# 1__schdoc.net
KiCad netlist of a schematic drawn in Altium Designer
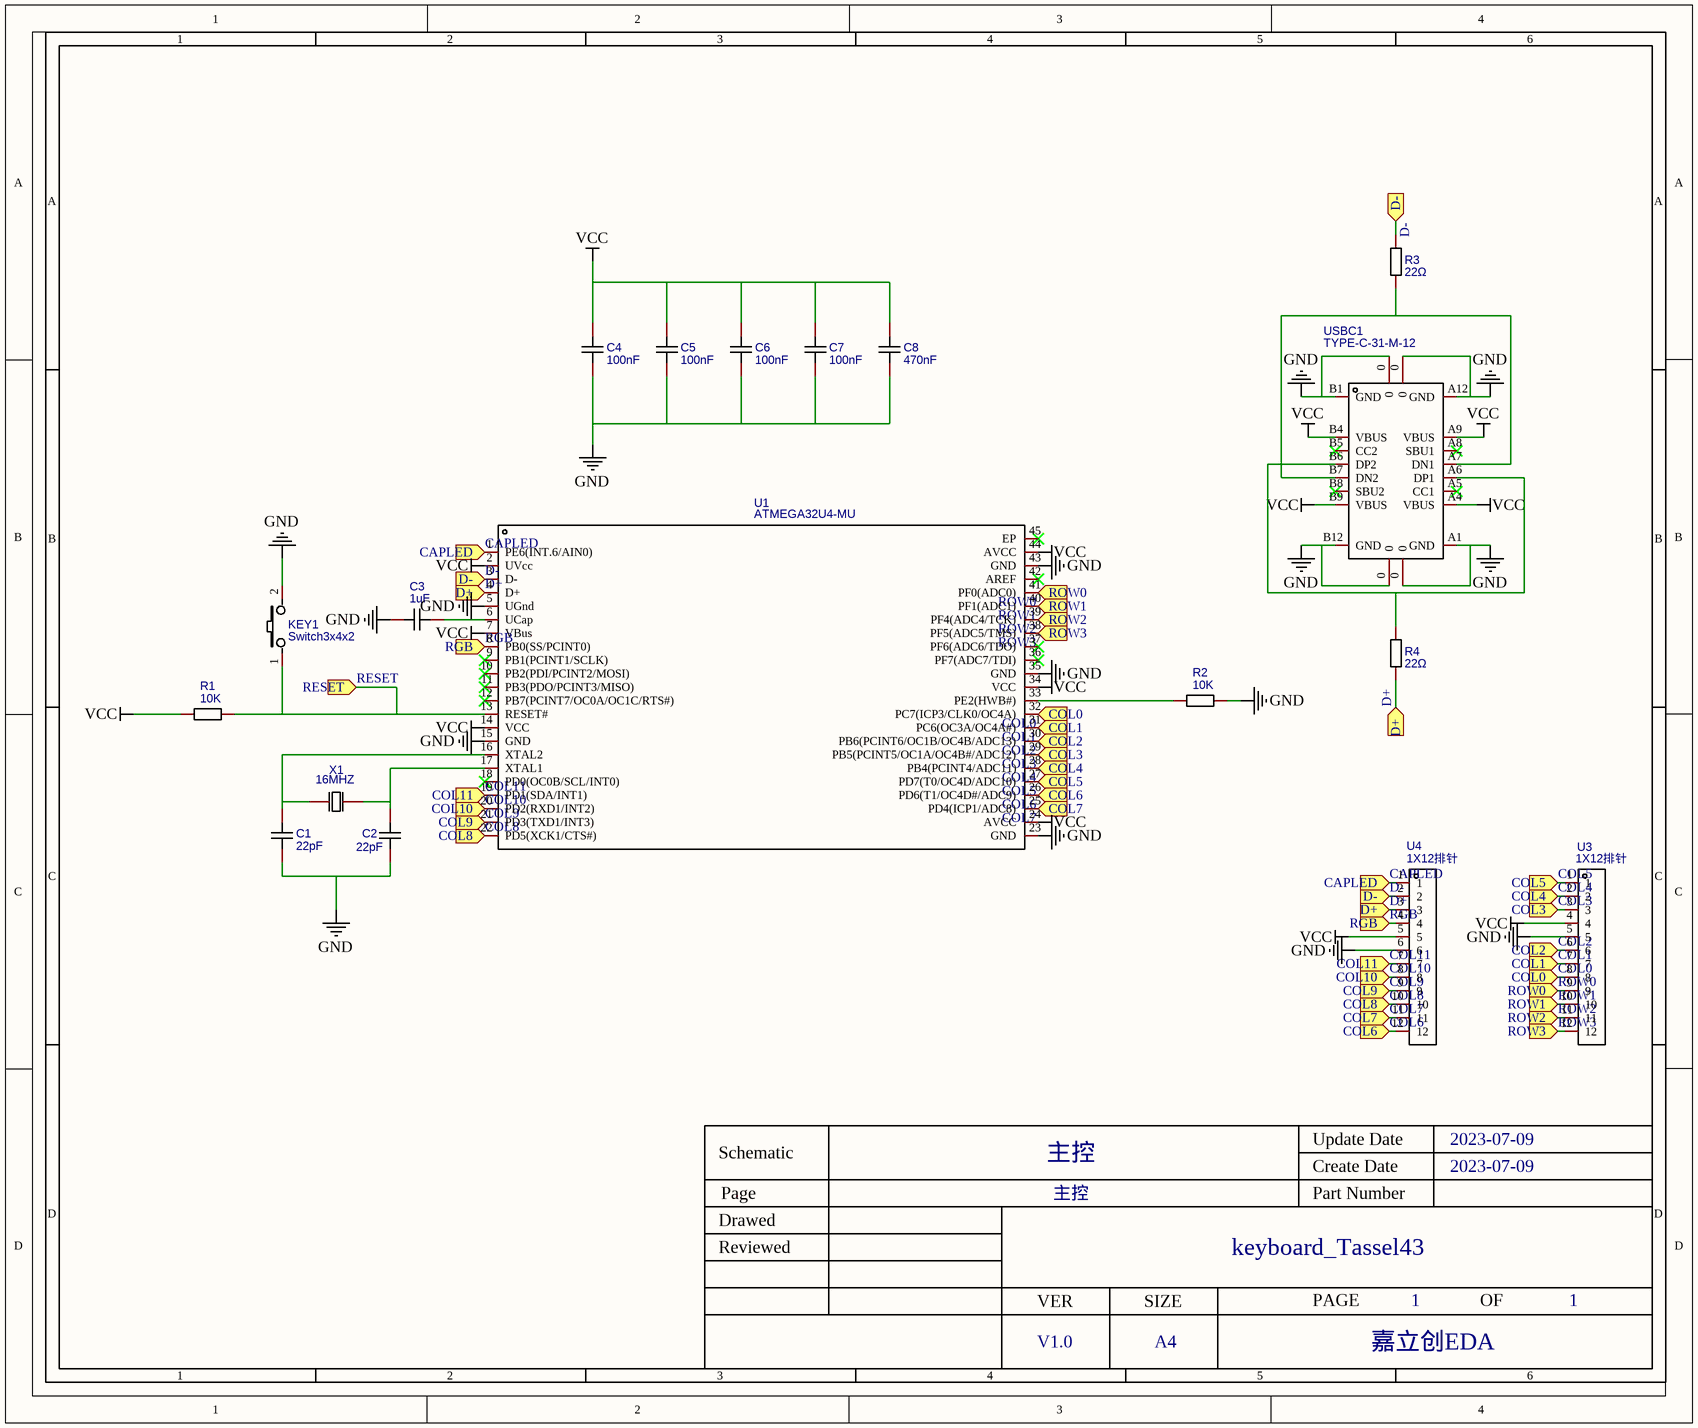
[diagram p0: 1_主控.schdoc.schdoc]

(export (version "E")
  (design (tool "Eeschema 10.0.6"))
  (components
    (comp (ref "C1")
      (value "22pF")
      (fields
        (field (name "NAME") "22pF")
        (field (name "MANUFACTURER") "Huaxin ST")
        (field (name "MANUFACTURER PART") "0603N220F101CT")
      )
      (libsource (lib "altium-import") (part "root_0_0603N220F101CT_"))
    )
    (comp (ref "C2")
      (value "22pF")
      (fields
        (field (name "NAME") "22pF")
        (field (name "MANUFACTURER") "Huaxin ST")
        (field (name "MANUFACTURER PART") "0603N220F101CT")
      )
      (libsource (lib "altium-import") (part "root_0_0603N220F101CT_"))
    )
    (comp (ref "C3")
      (value "1uF")
      (fields
        (field (name "NAME") "1uF")
        (field (name "MANUFACTURER") "FH")
        (field (name "MANUFACTURER PART") "0603B105K500NT")
      )
      (libsource (lib "altium-import") (part "root_0_0603B105K500NT_"))
    )
    (comp (ref "C4")
      (value "100nF")
      (fields
        (field (name "NAME") "100nF")
        (field (name "MANUFACTURER") "FH")
        (field (name "MANUFACTURER PART") "0603B104J500NT")
      )
      (libsource (lib "altium-import") (part "root_1_0603B104J500NT_"))
    )
    (comp (ref "C5")
      (value "100nF")
      (fields
        (field (name "NAME") "100nF")
        (field (name "MANUFACTURER") "FH")
        (field (name "MANUFACTURER PART") "0603B104J500NT")
      )
      (libsource (lib "altium-import") (part "root_1_0603B104J500NT_"))
    )
    (comp (ref "C6")
      (value "100nF")
      (fields
        (field (name "NAME") "100nF")
        (field (name "MANUFACTURER") "FH")
        (field (name "MANUFACTURER PART") "0603B104J500NT")
      )
      (libsource (lib "altium-import") (part "root_1_0603B104J500NT_"))
    )
    (comp (ref "C7")
      (value "100nF")
      (fields
        (field (name "NAME") "100nF")
        (field (name "MANUFACTURER") "FH")
        (field (name "MANUFACTURER PART") "0603B104J500NT")
      )
      (libsource (lib "altium-import") (part "root_1_0603B104J500NT_"))
    )
    (comp (ref "C8")
      (value "470nF")
      (fields
        (field (name "NAME") "470nF")
        (field (name "MANUFACTURER") "FH")
        (field (name "MANUFACTURER PART") "0603B474K250NT")
      )
      (libsource (lib "altium-import") (part "root_1_0603B474K250NT_"))
    )
    (comp (ref "KEY1")
      (value "Switch3x4x2")
      (fields (field (name "NAME") "Switch3x4x2") (field (name "MANUFACTURER") "ReliaPro"))
      (libsource (lib "altium-import") (part "root_1_Switch3x4x2_"))
    )
    (comp (ref "R1")
      (value "10K")
      (fields
        (field (name "NAME") "10K")
        (field (name "MANUFACTURER") "YAGEO")
        (field (name "MANUFACTURER PART") "AC0603FR-0710KL")
      )
      (libsource (lib "altium-import") (part "root_0_AC0603FR-0710KL_"))
    )
    (comp (ref "R2")
      (value "10K")
      (fields
        (field (name "NAME") "10K")
        (field (name "MANUFACTURER") "YAGEO")
        (field (name "MANUFACTURER PART") "AC0603FR-0710KL")
      )
      (libsource (lib "altium-import") (part "root_0_AC0603FR-0710KL_"))
    )
    (comp (ref "R3")
      (value "22Ω")
      (fields
        (field (name "NAME") "22Ω")
        (field (name "MANUFACTURER") "LIZ")
        (field (name "MANUFACTURER PART") "CR0603JA0220G")
      )
      (libsource (lib "altium-import") (part "root_1_CR0603JA0220G_"))
    )
    (comp (ref "R4")
      (value "22Ω")
      (fields
        (field (name "NAME") "22Ω")
        (field (name "MANUFACTURER") "LIZ")
        (field (name "MANUFACTURER PART") "CR0603JA0220G")
      )
      (libsource (lib "altium-import") (part "root_1_CR0603JA0220G_"))
    )
    (comp (ref "U1")
      (value "ATMEGA32U4-MU")
      (fields (field (name "NAME") "ATMEGA32U4-MU") (field (name "MANUFACTURER") "MICROCHIP"))
      (libsource (lib "altium-import") (part "root_0_ATMEGA32U4-MU_"))
    )
    (comp (ref "U3")
      (value "1X12排针")
      (fields (field (name "NAME") "1X12排针"))
      (libsource (lib "altium-import") (part "root_0_1X12排针_"))
    )
    (comp (ref "U4")
      (value "1X12排针")
      (fields (field (name "NAME") "1X12排针"))
      (libsource (lib "altium-import") (part "root_0_1X12排针_"))
    )
    (comp (ref "USBC1")
      (value "TYPE-C-31-M-12")
      (fields
        (field (name "NAME") "TYPE-C-31-M-12")
        (field (name "MANUFACTURER") "RectangularConnectors-Contacts")
      )
      (libsource (lib "altium-import") (part "root_0_TYPE-C-31-M-12_"))
    )
    (comp (ref "X1")
      (value "16MHZ")
      (fields
        (field (name "NAME") "16MHZ")
        (field (name "MANUFACTURER") "TAITIEN Elec")
        (field (name "MANUFACTURER PART") "XSHEELNANF-16MHZ")
      )
      (libsource (lib "altium-import") (part "root_0_XSHEELNANF-16MHZ_"))
    )
  )
  (nets
    (net (code "1") (name "/CAPLED") (class "Default")
      (node (ref "U1") (pin "1") (pinfunction "PE6(INT.6/AIN0)_1") (pintype "passive"))
      (node (ref "U4") (pin "1") (pinfunction "1_1") (pintype "passive"))
    )
    (net (code "2") (name "/COL0") (class "Default")
      (node (ref "U1") (pin "32") (pinfunction "PC7(ICP3/CLK0/OC4A)_32") (pintype "passive"))
      (node (ref "U3") (pin "8") (pinfunction "8_8") (pintype "passive"))
    )
    (net (code "3") (name "/COL1") (class "Default")
      (node (ref "U1") (pin "31") (pinfunction "PC6(OC3A/OC4A#)_31") (pintype "passive"))
      (node (ref "U3") (pin "7") (pinfunction "7_7") (pintype "passive"))
    )
    (net (code "4") (name "/COL2") (class "Default")
      (node (ref "U1") (pin "30") (pinfunction "PB6(PCINT6/OC1B/OC4B/ADC13)_30") (pintype "passive"))
      (node (ref "U3") (pin "6") (pinfunction "6_6") (pintype "passive"))
    )
    (net (code "5") (name "/COL3") (class "Default")
      (node (ref "U1") (pin "29") (pinfunction "PB5(PCINT5/OC1A/OC4B#/ADC12)_29") (pintype "passive"))
      (node (ref "U3") (pin "3") (pinfunction "3_3") (pintype "passive"))
    )
    (net (code "6") (name "/COL4") (class "Default")
      (node (ref "U1") (pin "28") (pinfunction "PB4(PCINT4/ADC11)_28") (pintype "passive"))
      (node (ref "U3") (pin "2") (pinfunction "2_2") (pintype "passive"))
    )
    (net (code "7") (name "/COL5") (class "Default")
      (node (ref "U1") (pin "27") (pinfunction "PD7(T0/OC4D/ADC10)_27") (pintype "passive"))
      (node (ref "U3") (pin "1") (pinfunction "1_1") (pintype "passive"))
    )
    (net (code "8") (name "/COL6") (class "Default")
      (node (ref "U1") (pin "26") (pinfunction "PD6(T1/OC4D#/ADC9)_26") (pintype "passive"))
      (node (ref "U4") (pin "12") (pinfunction "12_12") (pintype "passive"))
    )
    (net (code "9") (name "/COL7") (class "Default")
      (node (ref "U1") (pin "25") (pinfunction "PD4(ICP1/ADC8)_25") (pintype "passive"))
      (node (ref "U4") (pin "11") (pinfunction "11_11") (pintype "passive"))
    )
    (net (code "10") (name "/COL8") (class "Default")
      (node (ref "U1") (pin "22") (pinfunction "PD5(XCK1/CTS#)_22") (pintype "passive"))
      (node (ref "U4") (pin "10") (pinfunction "10_10") (pintype "passive"))
    )
    (net (code "11") (name "/COL9") (class "Default")
      (node (ref "U1") (pin "21") (pinfunction "PD3(TXD1/INT3)_21") (pintype "passive"))
      (node (ref "U4") (pin "9") (pinfunction "9_9") (pintype "passive"))
    )
    (net (code "12") (name "/COL10") (class "Default")
      (node (ref "U1") (pin "20") (pinfunction "PD2(RXD1/INT2)_20") (pintype "passive"))
      (node (ref "U4") (pin "8") (pinfunction "8_8") (pintype "passive"))
    )
    (net (code "13") (name "/COL11") (class "Default")
      (node (ref "U1") (pin "19") (pinfunction "PD1(SDA/INT1)_19") (pintype "passive"))
      (node (ref "U4") (pin "7") (pinfunction "7_7") (pintype "passive"))
    )
    (net (code "14") (name "/D+") (class "Default")
      (node (ref "R4") (pin "1") (pinfunction "1_1") (pintype "passive"))
      (node (ref "U1") (pin "4") (pinfunction "D+_4") (pintype "passive"))
      (node (ref "U4") (pin "3") (pinfunction "3_3") (pintype "passive"))
    )
    (net (code "15") (name "/D-") (class "Default")
      (node (ref "R3") (pin "2") (pinfunction "2_2") (pintype "passive"))
      (node (ref "U1") (pin "3") (pinfunction "D-_3") (pintype "passive"))
      (node (ref "U4") (pin "2") (pinfunction "2_2") (pintype "passive"))
    )
    (net (code "16") (name "/RESET") (class "Default")
      (node (ref "KEY1") (pin "1") (pinfunction "1_1") (pintype "passive"))
      (node (ref "R1") (pin "2") (pinfunction "2_2") (pintype "passive"))
      (node (ref "U1") (pin "13") (pinfunction "RESET#_13") (pintype "passive"))
    )
    (net (code "17") (name "/RGB") (class "Default")
      (node (ref "U1") (pin "8") (pinfunction "PB0(SS/PCINT0)_8") (pintype "passive"))
      (node (ref "U4") (pin "4") (pinfunction "4_4") (pintype "passive"))
    )
    (net (code "18") (name "/ROW0") (class "Default")
      (node (ref "U1") (pin "41") (pinfunction "PF0(ADC0)_41") (pintype "passive"))
      (node (ref "U3") (pin "9") (pinfunction "9_9") (pintype "passive"))
    )
    (net (code "19") (name "/ROW1") (class "Default")
      (node (ref "U1") (pin "40") (pinfunction "PF1(ADC1)_40") (pintype "passive"))
      (node (ref "U3") (pin "10") (pinfunction "10_10") (pintype "passive"))
    )
    (net (code "20") (name "/ROW2") (class "Default")
      (node (ref "U1") (pin "39") (pinfunction "PF4(ADC4/TCK)_39") (pintype "passive"))
      (node (ref "U3") (pin "11") (pinfunction "11_11") (pintype "passive"))
    )
    (net (code "21") (name "/ROW3") (class "Default")
      (node (ref "U1") (pin "38") (pinfunction "PF5(ADC5/TMS)_38") (pintype "passive"))
      (node (ref "U3") (pin "12") (pinfunction "12_12") (pintype "passive"))
    )
    (net (code "22") (name "GND") (class "Default")
      (node (ref "C1") (pin "1") (pinfunction "1_1") (pintype "passive"))
      (node (ref "C2") (pin "1") (pinfunction "1_1") (pintype "passive"))
      (node (ref "C3") (pin "1") (pinfunction "1_1") (pintype "passive"))
      (node (ref "C4") (pin "1") (pinfunction "1_1") (pintype "passive"))
      (node (ref "C5") (pin "1") (pinfunction "1_1") (pintype "passive"))
      (node (ref "C6") (pin "1") (pinfunction "1_1") (pintype "passive"))
      (node (ref "C7") (pin "1") (pinfunction "1_1") (pintype "passive"))
      (node (ref "C8") (pin "2") (pinfunction "2_2") (pintype "passive"))
      (node (ref "KEY1") (pin "2") (pinfunction "2_2") (pintype "passive"))
      (node (ref "R2") (pin "2") (pinfunction "2_2") (pintype "passive"))
      (node (ref "U1") (pin "15") (pinfunction "GND_15") (pintype "passive"))
      (node (ref "U1") (pin "23") (pinfunction "GND_23") (pintype "passive"))
      (node (ref "U1") (pin "35") (pinfunction "GND_35") (pintype "passive"))
      (node (ref "U1") (pin "43") (pinfunction "GND_43") (pintype "passive"))
      (node (ref "U1") (pin "5") (pinfunction "UGnd_5") (pintype "passive"))
      (node (ref "U3") (pin "5") (pinfunction "5_5") (pintype "passive"))
      (node (ref "U4") (pin "6") (pinfunction "6_6") (pintype "passive"))
      (node (ref "USBC1") (pin "0") (pinfunction "0_0") (pintype "passive"))
      (node (ref "USBC1") (pin "A1") (pinfunction "GND_A1") (pintype "passive"))
      (node (ref "USBC1") (pin "A12") (pinfunction "GND_A12") (pintype "passive"))
      (node (ref "USBC1") (pin "B1") (pinfunction "GND_B1") (pintype "passive"))
      (node (ref "USBC1") (pin "B12") (pinfunction "GND_B12") (pintype "passive"))
    )
    (net (code "23") (name "Net-(U1-PE2(HWB#))") (class "Default")
      (node (ref "R2") (pin "1") (pinfunction "1_1") (pintype "passive"))
      (node (ref "U1") (pin "33") (pinfunction "PE2(HWB#)_33") (pintype "passive"))
    )
    (net (code "24") (name "Net-(U1-UCap)") (class "Default")
      (node (ref "C3") (pin "2") (pinfunction "2_2") (pintype "passive"))
      (node (ref "U1") (pin "6") (pinfunction "UCap_6") (pintype "passive"))
    )
    (net (code "25") (name "Net-(U1-XTAL1)") (class "Default")
      (node (ref "C2") (pin "2") (pinfunction "2_2") (pintype "passive"))
      (node (ref "U1") (pin "17") (pinfunction "XTAL1_17") (pintype "passive"))
      (node (ref "X1") (pin "2") (pinfunction "OSC2_2") (pintype "passive"))
    )
    (net (code "26") (name "Net-(U1-XTAL2)") (class "Default")
      (node (ref "C1") (pin "2") (pinfunction "2_2") (pintype "passive"))
      (node (ref "U1") (pin "16") (pinfunction "XTAL2_16") (pintype "passive"))
      (node (ref "X1") (pin "1") (pinfunction "OSC1_1") (pintype "passive"))
    )
    (net (code "27") (name "Net-(USBC1-DN1)") (class "Default")
      (node (ref "R3") (pin "1") (pinfunction "1_1") (pintype "passive"))
      (node (ref "USBC1") (pin "A7") (pinfunction "DN1_A7") (pintype "passive"))
      (node (ref "USBC1") (pin "B7") (pinfunction "DN2_B7") (pintype "passive"))
    )
    (net (code "28") (name "Net-(USBC1-DP1)") (class "Default")
      (node (ref "R4") (pin "2") (pinfunction "2_2") (pintype "passive"))
      (node (ref "USBC1") (pin "A6") (pinfunction "DP1_A6") (pintype "passive"))
      (node (ref "USBC1") (pin "B6") (pinfunction "DP2_B6") (pintype "passive"))
    )
    (net (code "29") (name "VCC") (class "Default")
      (node (ref "C4") (pin "2") (pinfunction "2_2") (pintype "passive"))
      (node (ref "C5") (pin "2") (pinfunction "2_2") (pintype "passive"))
      (node (ref "C6") (pin "2") (pinfunction "2_2") (pintype "passive"))
      (node (ref "C7") (pin "2") (pinfunction "2_2") (pintype "passive"))
      (node (ref "C8") (pin "1") (pinfunction "1_1") (pintype "passive"))
      (node (ref "R1") (pin "1") (pinfunction "1_1") (pintype "passive"))
      (node (ref "U1") (pin "14") (pinfunction "VCC_14") (pintype "passive"))
      (node (ref "U1") (pin "2") (pinfunction "UVcc_2") (pintype "passive"))
      (node (ref "U1") (pin "24") (pinfunction "AVCC_24") (pintype "passive"))
      (node (ref "U1") (pin "34") (pinfunction "VCC_34") (pintype "passive"))
      (node (ref "U1") (pin "44") (pinfunction "AVCC_44") (pintype "passive"))
      (node (ref "U1") (pin "7") (pinfunction "VBus_7") (pintype "passive"))
      (node (ref "U3") (pin "4") (pinfunction "4_4") (pintype "passive"))
      (node (ref "U4") (pin "5") (pinfunction "5_5") (pintype "passive"))
      (node (ref "USBC1") (pin "A4") (pinfunction "VBUS_A4") (pintype "passive"))
      (node (ref "USBC1") (pin "A9") (pinfunction "VBUS_A9") (pintype "passive"))
      (node (ref "USBC1") (pin "B4") (pinfunction "VBUS_B4") (pintype "passive"))
      (node (ref "USBC1") (pin "B9") (pinfunction "VBUS_B9") (pintype "passive"))
    )
    (net (code "30") (name "unconnected-(U1-AREF-Pad42)") (class "Default")
      (node (ref "U1") (pin "42") (pinfunction "AREF_42") (pintype "passive+no_connect"))
    )
    (net (code "31") (name "unconnected-(U1-EP-Pad45)") (class "Default")
      (node (ref "U1") (pin "45") (pinfunction "EP_45") (pintype "passive+no_connect"))
    )
    (net (code "32") (name "unconnected-(U1-PB1(PCINT1{slash}SCLK)-Pad9)") (class "Default")
      (node (ref "U1") (pin "9") (pinfunction "PB1(PCINT1/SCLK)_9") (pintype "passive+no_connect"))
    )
    (net (code "33") (name "unconnected-(U1-PB2(PDI{slash}PCINT2{slash}MOSI)-Pad10)") (class "Default")
      (node (ref "U1") (pin "10") (pinfunction "PB2(PDI/PCINT2/MOSI)_10") (pintype "passive+no_connect"))
    )
    (net (code "34") (name "unconnected-(U1-PB3(PDO{slash}PCINT3{slash}MISO)-Pad11)") (class "Default")
      (node (ref "U1") (pin "11") (pinfunction "PB3(PDO/PCINT3/MISO)_11") (pintype "passive+no_connect"))
    )
    (net (code "35") (name "unconnected-(U1-PB7(PCINT7{slash}OC0A{slash}OC1C{slash}RTS#)-Pad12)") (class "Default")
      (node (ref "U1") (pin "12") (pinfunction "PB7(PCINT7/OC0A/OC1C/RTS#)_12") (pintype "passive+no_connect"))
    )
    (net (code "36") (name "unconnected-(U1-PD0(OC0B{slash}SCL{slash}INT0)-Pad18)") (class "Default")
      (node (ref "U1") (pin "18") (pinfunction "PD0(OC0B/SCL/INT0)_18") (pintype "passive+no_connect"))
    )
    (net (code "37") (name "unconnected-(U1-PF6(ADC6{slash}TDO)-Pad37)") (class "Default")
      (node (ref "U1") (pin "37") (pinfunction "PF6(ADC6/TDO)_37") (pintype "passive+no_connect"))
    )
    (net (code "38") (name "unconnected-(U1-PF7(ADC7{slash}TDI)-Pad36)") (class "Default")
      (node (ref "U1") (pin "36") (pinfunction "PF7(ADC7/TDI)_36") (pintype "passive+no_connect"))
    )
    (net (code "39") (name "unconnected-(USBC1-CC1-PadA5)") (class "Default")
      (node (ref "USBC1") (pin "A5") (pinfunction "CC1_A5") (pintype "passive+no_connect"))
    )
    (net (code "40") (name "unconnected-(USBC1-CC2-PadB5)") (class "Default")
      (node (ref "USBC1") (pin "B5") (pinfunction "CC2_B5") (pintype "passive+no_connect"))
    )
    (net (code "41") (name "unconnected-(USBC1-SBU1-PadA8)") (class "Default")
      (node (ref "USBC1") (pin "A8") (pinfunction "SBU1_A8") (pintype "passive+no_connect"))
    )
    (net (code "42") (name "unconnected-(USBC1-SBU2-PadB8)") (class "Default")
      (node (ref "USBC1") (pin "B8") (pinfunction "SBU2_B8") (pintype "passive+no_connect"))
    )
  )
)
